# Sheet1.net
KiCad netlist of a schematic drawn in Altium Designer
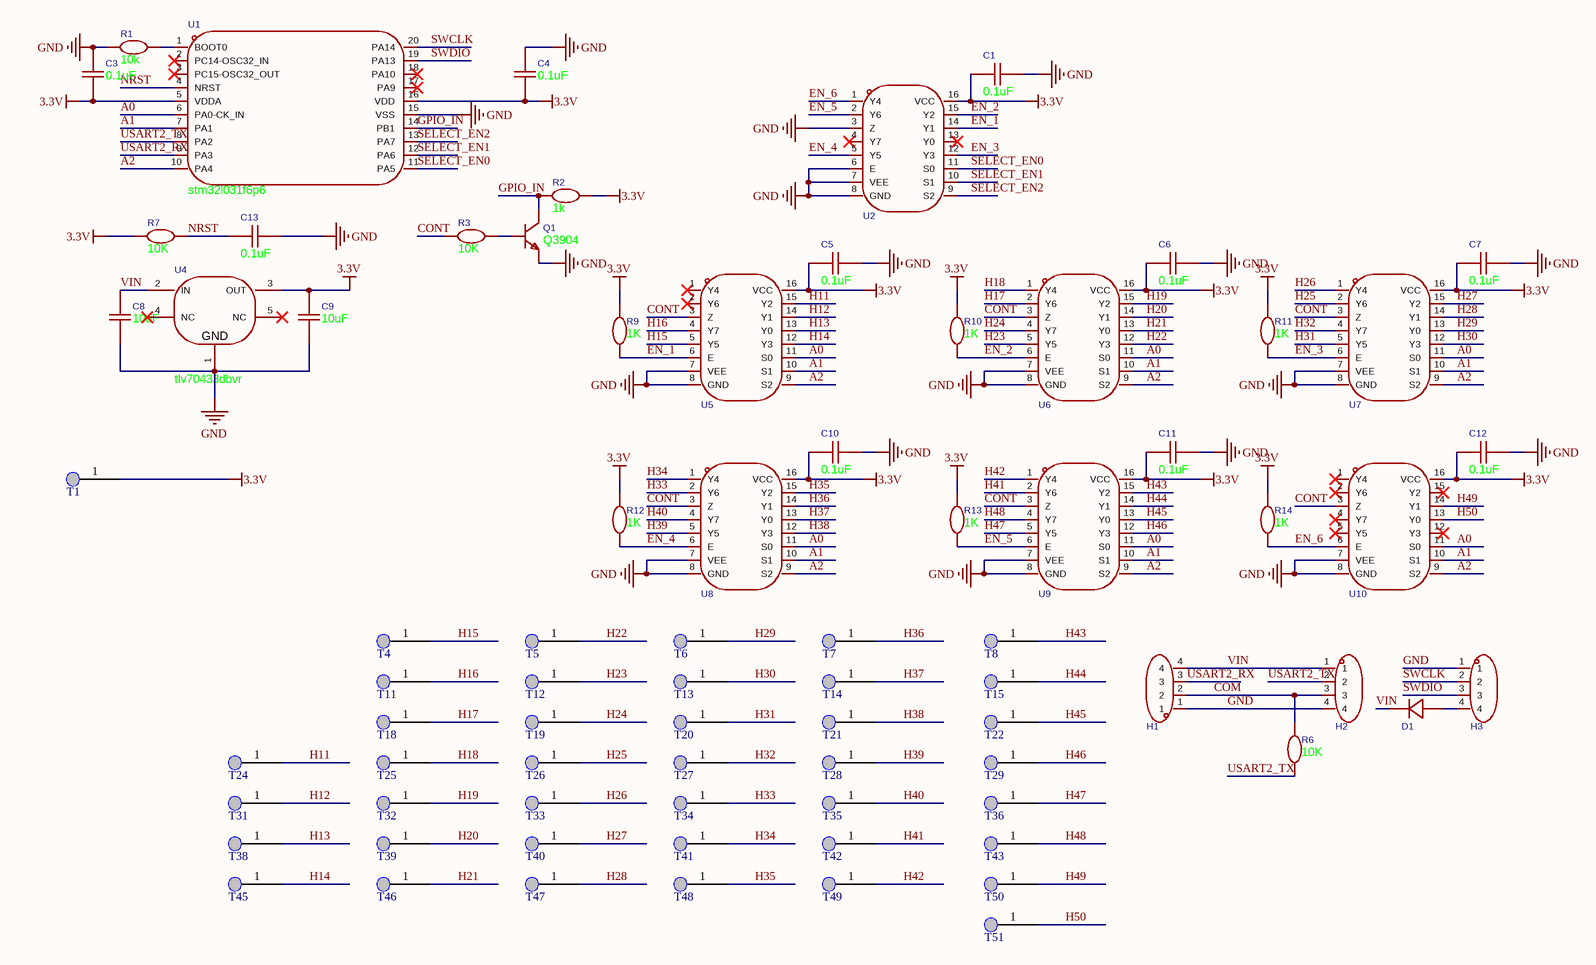
[diagram p0: Sheet1.SchDoc]

(export (version "E")
  (design (tool "Eeschema 10.0.6"))
  (components
    (comp (ref "C1")
      (value "0.1uF")
      (footprint "C0603")
      (description "容值:100nF;精度:±10%;额定电压:50V;温度系数:X7R;")
      (fields (field (name "MANUFACTURER") "SAMSUNG(三星)") (field (name "MANUFACTURERPART") "CL10B104KB8NNNC"))
      (libsource (lib "Schlib1") (part "C"))
    )
    (comp (ref "C3")
      (value "0.1uF")
      (footprint "C0603")
      (description "容值:100nF;精度:±10%;额定电压:50V;温度系数:X7R;")
      (fields (field (name "MANUFACTURER") "SAMSUNG(三星)") (field (name "MANUFACTURERPART") "CL10B104KB8NNNC"))
      (libsource (lib "Schlib1") (part "C"))
    )
    (comp (ref "C4")
      (value "0.1uF")
      (footprint "C0603")
      (description "容值:100nF;精度:±10%;额定电压:50V;温度系数:X7R;")
      (fields (field (name "MANUFACTURER") "SAMSUNG(三星)") (field (name "MANUFACTURERPART") "CL10B104KB8NNNC"))
      (libsource (lib "Schlib1") (part "C"))
    )
    (comp (ref "C5")
      (value "0.1uF")
      (footprint "C0603")
      (description "容值:100nF;精度:±10%;额定电压:50V;温度系数:X7R;")
      (fields (field (name "MANUFACTURER") "SAMSUNG(三星)") (field (name "MANUFACTURERPART") "CL10B104KB8NNNC"))
      (libsource (lib "Schlib1") (part "C"))
    )
    (comp (ref "C6")
      (value "0.1uF")
      (footprint "C0603")
      (description "容值:100nF;精度:±10%;额定电压:50V;温度系数:X7R;")
      (fields (field (name "MANUFACTURER") "SAMSUNG(三星)") (field (name "MANUFACTURERPART") "CL10B104KB8NNNC"))
      (libsource (lib "Schlib1") (part "C"))
    )
    (comp (ref "C7")
      (value "0.1uF")
      (footprint "C0603")
      (description "容值:100nF;精度:±10%;额定电压:50V;温度系数:X7R;")
      (fields (field (name "MANUFACTURER") "SAMSUNG(三星)") (field (name "MANUFACTURERPART") "CL10B104KB8NNNC"))
      (libsource (lib "Schlib1") (part "C"))
    )
    (comp (ref "C8")
      (value "10uF")
      (footprint "C0603")
      (description "容值:100nF;精度:±10%;额定电压:50V;温度系数:X7R;")
      (fields (field (name "MANUFACTURER") "SAMSUNG(三星)") (field (name "MANUFACTURERPART") "CL10B104KB8NNNC"))
      (libsource (lib "Schlib1") (part "C"))
    )
    (comp (ref "C9")
      (value "10uF")
      (footprint "C0603")
      (description "容值:100nF;精度:±10%;额定电压:50V;温度系数:X7R;")
      (fields (field (name "MANUFACTURER") "SAMSUNG(三星)") (field (name "MANUFACTURERPART") "CL10B104KB8NNNC"))
      (libsource (lib "Schlib1") (part "C"))
    )
    (comp (ref "C10")
      (value "0.1uF")
      (footprint "C0603")
      (description "容值:100nF;精度:±10%;额定电压:50V;温度系数:X7R;")
      (fields (field (name "MANUFACTURER") "SAMSUNG(三星)") (field (name "MANUFACTURERPART") "CL10B104KB8NNNC"))
      (libsource (lib "Schlib1") (part "C"))
    )
    (comp (ref "C11")
      (value "0.1uF")
      (footprint "C0603")
      (description "容值:100nF;精度:±10%;额定电压:50V;温度系数:X7R;")
      (fields (field (name "MANUFACTURER") "SAMSUNG(三星)") (field (name "MANUFACTURERPART") "CL10B104KB8NNNC"))
      (libsource (lib "Schlib1") (part "C"))
    )
    (comp (ref "C12")
      (value "0.1uF")
      (footprint "C0603")
      (description "容值:100nF;精度:±10%;额定电压:50V;温度系数:X7R;")
      (fields (field (name "MANUFACTURER") "SAMSUNG(三星)") (field (name "MANUFACTURERPART") "CL10B104KB8NNNC"))
      (libsource (lib "Schlib1") (part "C"))
    )
    (comp (ref "C13")
      (value "0.1uF")
      (footprint "C0603")
      (description "容值:100nF;精度:±10%;额定电压:50V;温度系数:X7R;")
      (fields (field (name "MANUFACTURER") "SAMSUNG(三星)") (field (name "MANUFACTURERPART") "CL10B104KB8NNNC"))
      (libsource (lib "Schlib1") (part "C"))
    )
    (comp (ref "D1")
      (value "1n4148ws_c7420319")
      (footprint "SOD-323_L1.7-W1.3-LS2.5-FD")
      (description "二极管配置:独立式;整流电流:150mA;直流反向耐压(Vr):100V;正向压降(Vf):1.25V@150mA;反向恢复时间(Trr):4ns;")
      (fields (field (name "MANUFACTURER") "R+O(宏嘉诚)") (field (name "MANUFACTURERPART") "1N4148WS"))
      (libsource (lib "Schlib1") (part "1n4148ws_c7420319"))
    )
    (comp (ref "H1")
      (value "pz254v-11-04p")
      (footprint "HDR-TH_4P-P2.54-V-M")
      (fields (field (name "MANUFACTURER") "XFCN(兴飞)") (field (name "MANUFACTURERPART") "PZ254V-11-04P"))
      (libsource (lib "Schlib1") (part "pz254v-11-04p"))
    )
    (comp (ref "H2")
      (value "pz254v-11-04p")
      (footprint "HDR-TH_4P-P2.54-V-M")
      (fields (field (name "MANUFACTURER") "XFCN(兴飞)") (field (name "MANUFACTURERPART") "PZ254V-11-04P"))
      (libsource (lib "Schlib1") (part "pz254v-11-04p"))
    )
    (comp (ref "H3")
      (value "pz254v-11-04p")
      (footprint "HDR-TH_4P-P2.54-V-M")
      (fields (field (name "MANUFACTURER") "XFCN(兴飞)") (field (name "MANUFACTURERPART") "PZ254V-11-04P"))
      (libsource (lib "Schlib1") (part "pz254v-11-04p"))
    )
    (comp (ref "Q1")
      (value "Q3904")
      (footprint "SOT-23-3_L2.9-W1.6-P1.90-LS2.8-BR")
      (description "晶体管类型:NPN;集电极电流(Ic):200mA;集射极击穿电压(Vceo):40V;耗散功率(Pd):225mW;直流电流增益(hFE):40@0.1mA,1.0V;")
      (fields (field (name "MANUFACTURER") "onsemi(安森美)") (field (name "MANUFACTURERPART") "MMBT3904LT1G"))
      (libsource (lib "Schlib1") (part "Q3904"))
    )
    (comp (ref "R1")
      (value "10k")
      (footprint "R0603")
      (description "电阻类型:厚膜电阻;阻值:1kΩ;精度:±1%;功率:100mW;工作电压:75V;温度系数:±100ppm/℃;")
      (fields (field (name "MANUFACTURER") "FOJAN(富捷)") (field (name "MANUFACTURERPART") "FRC0603F1001TS"))
      (libsource (lib "Schlib1") (part "R"))
    )
    (comp (ref "R2")
      (value "1k")
      (footprint "R0603")
      (description "电阻类型:厚膜电阻;阻值:1kΩ;精度:±1%;功率:100mW;工作电压:75V;温度系数:±100ppm/℃;")
      (fields (field (name "MANUFACTURER") "FOJAN(富捷)") (field (name "MANUFACTURERPART") "FRC0603F1001TS"))
      (libsource (lib "Schlib1") (part "R"))
    )
    (comp (ref "R3")
      (value "10K")
      (footprint "R0603")
      (description "电阻类型:厚膜电阻;阻值:1kΩ;精度:±1%;功率:100mW;工作电压:75V;温度系数:±100ppm/℃;")
      (fields (field (name "MANUFACTURER") "FOJAN(富捷)") (field (name "MANUFACTURERPART") "FRC0603F1001TS"))
      (libsource (lib "Schlib1") (part "R"))
    )
    (comp (ref "R6")
      (value "10K")
      (footprint "R0805")
      (description "电阻类型:厚膜电阻;阻值:1kΩ;精度:±1%;功率:100mW;工作电压:75V;温度系数:±100ppm/℃;")
      (fields (field (name "MANUFACTURER") "FOJAN(富捷)") (field (name "MANUFACTURERPART") "FRC0603F1001TS"))
      (libsource (lib "Schlib1") (part "R"))
    )
    (comp (ref "R7")
      (value "10K")
      (footprint "R0603")
      (description "电阻类型:厚膜电阻;阻值:1kΩ;精度:±1%;功率:100mW;工作电压:75V;温度系数:±100ppm/℃;")
      (fields (field (name "MANUFACTURER") "FOJAN(富捷)") (field (name "MANUFACTURERPART") "FRC0603F1001TS"))
      (libsource (lib "Schlib1") (part "R"))
    )
    (comp (ref "R9")
      (value "1K")
      (footprint "R0603")
      (description "电阻类型:厚膜电阻;阻值:1kΩ;精度:±1%;功率:100mW;工作电压:75V;温度系数:±100ppm/℃;")
      (fields (field (name "MANUFACTURER") "FOJAN(富捷)") (field (name "MANUFACTURERPART") "FRC0603F1001TS"))
      (libsource (lib "Schlib1") (part "R"))
    )
    (comp (ref "R10")
      (value "1K")
      (footprint "R0603")
      (description "电阻类型:厚膜电阻;阻值:1kΩ;精度:±1%;功率:100mW;工作电压:75V;温度系数:±100ppm/℃;")
      (fields (field (name "MANUFACTURER") "FOJAN(富捷)") (field (name "MANUFACTURERPART") "FRC0603F1001TS"))
      (libsource (lib "Schlib1") (part "R"))
    )
    (comp (ref "R11")
      (value "1K")
      (footprint "R0603")
      (description "电阻类型:厚膜电阻;阻值:1kΩ;精度:±1%;功率:100mW;工作电压:75V;温度系数:±100ppm/℃;")
      (fields (field (name "MANUFACTURER") "FOJAN(富捷)") (field (name "MANUFACTURERPART") "FRC0603F1001TS"))
      (libsource (lib "Schlib1") (part "R"))
    )
    (comp (ref "R12")
      (value "1K")
      (footprint "R0603")
      (description "电阻类型:厚膜电阻;阻值:1kΩ;精度:±1%;功率:100mW;工作电压:75V;温度系数:±100ppm/℃;")
      (fields (field (name "MANUFACTURER") "FOJAN(富捷)") (field (name "MANUFACTURERPART") "FRC0603F1001TS"))
      (libsource (lib "Schlib1") (part "R"))
    )
    (comp (ref "R13")
      (value "1K")
      (footprint "R0603")
      (description "电阻类型:厚膜电阻;阻值:1kΩ;精度:±1%;功率:100mW;工作电压:75V;温度系数:±100ppm/℃;")
      (fields (field (name "MANUFACTURER") "FOJAN(富捷)") (field (name "MANUFACTURERPART") "FRC0603F1001TS"))
      (libsource (lib "Schlib1") (part "R"))
    )
    (comp (ref "R14")
      (value "1K")
      (footprint "R0603")
      (description "电阻类型:厚膜电阻;阻值:1kΩ;精度:±1%;功率:100mW;工作电压:75V;温度系数:±100ppm/℃;")
      (fields (field (name "MANUFACTURER") "FOJAN(富捷)") (field (name "MANUFACTURERPART") "FRC0603F1001TS"))
      (libsource (lib "Schlib1") (part "R"))
    )
    (comp (ref "T1") (value "焊盘") (footprint "Contact") (libsource (lib "Schlib1") (part "PAD")))
    (comp (ref "T4") (value "焊盘") (footprint "Contact") (libsource (lib "Schlib1") (part "PAD")))
    (comp (ref "T5") (value "焊盘") (footprint "Contact") (libsource (lib "Schlib1") (part "PAD")))
    (comp (ref "T6") (value "焊盘") (footprint "Contact") (libsource (lib "Schlib1") (part "PAD")))
    (comp (ref "T7") (value "焊盘") (footprint "Contact") (libsource (lib "Schlib1") (part "PAD")))
    (comp (ref "T8") (value "焊盘") (footprint "Contact") (libsource (lib "Schlib1") (part "PAD")))
    (comp (ref "T11") (value "焊盘") (footprint "Contact") (libsource (lib "Schlib1") (part "PAD")))
    (comp (ref "T12") (value "焊盘") (footprint "Contact") (libsource (lib "Schlib1") (part "PAD")))
    (comp (ref "T13") (value "焊盘") (footprint "Contact") (libsource (lib "Schlib1") (part "PAD")))
    (comp (ref "T14") (value "焊盘") (footprint "Contact") (libsource (lib "Schlib1") (part "PAD")))
    (comp (ref "T15") (value "焊盘") (footprint "Contact") (libsource (lib "Schlib1") (part "PAD")))
    (comp (ref "T18") (value "焊盘") (footprint "Contact") (libsource (lib "Schlib1") (part "PAD")))
    (comp (ref "T19") (value "焊盘") (footprint "Contact") (libsource (lib "Schlib1") (part "PAD")))
    (comp (ref "T20") (value "焊盘") (footprint "Contact") (libsource (lib "Schlib1") (part "PAD")))
    (comp (ref "T21") (value "焊盘") (footprint "Contact") (libsource (lib "Schlib1") (part "PAD")))
    (comp (ref "T22") (value "焊盘") (footprint "Contact") (libsource (lib "Schlib1") (part "PAD")))
    (comp (ref "T24") (value "焊盘") (footprint "Contact") (libsource (lib "Schlib1") (part "PAD")))
    (comp (ref "T25") (value "焊盘") (footprint "Contact") (libsource (lib "Schlib1") (part "PAD")))
    (comp (ref "T26") (value "焊盘") (footprint "Contact") (libsource (lib "Schlib1") (part "PAD")))
    (comp (ref "T27") (value "焊盘") (footprint "Contact") (libsource (lib "Schlib1") (part "PAD")))
    (comp (ref "T28") (value "焊盘") (footprint "Contact") (libsource (lib "Schlib1") (part "PAD")))
    (comp (ref "T29") (value "焊盘") (footprint "Contact") (libsource (lib "Schlib1") (part "PAD")))
    (comp (ref "T31") (value "焊盘") (footprint "Contact") (libsource (lib "Schlib1") (part "PAD")))
    (comp (ref "T32") (value "焊盘") (footprint "Contact") (libsource (lib "Schlib1") (part "PAD")))
    (comp (ref "T33") (value "焊盘") (footprint "Contact") (libsource (lib "Schlib1") (part "PAD")))
    (comp (ref "T34") (value "焊盘") (footprint "Contact") (libsource (lib "Schlib1") (part "PAD")))
    (comp (ref "T35") (value "焊盘") (footprint "Contact") (libsource (lib "Schlib1") (part "PAD")))
    (comp (ref "T36") (value "焊盘") (footprint "Contact") (libsource (lib "Schlib1") (part "PAD")))
    (comp (ref "T38") (value "焊盘") (footprint "Contact") (libsource (lib "Schlib1") (part "PAD")))
    (comp (ref "T39") (value "焊盘") (footprint "Contact") (libsource (lib "Schlib1") (part "PAD")))
    (comp (ref "T40") (value "焊盘") (footprint "Contact") (libsource (lib "Schlib1") (part "PAD")))
    (comp (ref "T41") (value "焊盘") (footprint "Contact") (libsource (lib "Schlib1") (part "PAD")))
    (comp (ref "T42") (value "焊盘") (footprint "Contact") (libsource (lib "Schlib1") (part "PAD")))
    (comp (ref "T43") (value "焊盘") (footprint "Contact") (libsource (lib "Schlib1") (part "PAD")))
    (comp (ref "T45") (value "焊盘") (footprint "Contact") (libsource (lib "Schlib1") (part "PAD")))
    (comp (ref "T46") (value "焊盘") (footprint "Contact") (libsource (lib "Schlib1") (part "PAD")))
    (comp (ref "T47") (value "焊盘") (footprint "Contact") (libsource (lib "Schlib1") (part "PAD")))
    (comp (ref "T48") (value "焊盘") (footprint "Contact") (libsource (lib "Schlib1") (part "PAD")))
    (comp (ref "T49") (value "焊盘") (footprint "Contact") (libsource (lib "Schlib1") (part "PAD")))
    (comp (ref "T50") (value "焊盘") (footprint "Contact") (libsource (lib "Schlib1") (part "PAD")))
    (comp (ref "T51") (value "焊盘") (footprint "Contact") (libsource (lib "Schlib1") (part "PAD")))
    (comp (ref "U1")
      (value "stm32l031f6p6")
      (footprint "TSSOP-20_L6.5-W4.4-P0.65-LS6.4-BL")
      (description "CPU内核:-;CPU最大主频:32MHz;")
      (fields (field (name "MANUFACTURER") "ST(意法半导体)") (field (name "MANUFACTURERPART") "STM32L031F6P6"))
      (libsource (lib "Schlib1") (part "stm32l031f6p6"))
    )
    (comp (ref "U2")
      (value "74hc4051d,653")
      (footprint "SOIC-16_L9.9-W3.9-P1.27-LS6.0-BL")
      (description "开关电路:8:1;通道数:1;导通电阻(Ron):80Ω;")
      (fields (field (name "MANUFACTURER") "Nexperia(安世)") (field (name "MANUFACTURERPART") "74HC4051D,653"))
      (libsource (lib "Schlib1") (part "74hc4051d,653"))
    )
    (comp (ref "U4")
      (value "tlv70433dbvr")
      (footprint "SOT-23-5_L3.0-W1.7-P0.95-LS2.8-BR")
      (description "输出极性:正极;工作电压:24V;输出电压:3.3V;输出电流:150mA;电源纹波抑制比(PSRR):60dB@(100kHz);输出类型:固定;")
      (fields (field (name "MANUFACTURER") "TI(德州仪器)") (field (name "MANUFACTURERPART") "TLV70433DBVR"))
      (libsource (lib "Schlib1") (part "tlv70433dbvr"))
    )
    (comp (ref "U5")
      (value "74hc4051d,653")
      (footprint "SOIC-16_L9.9-W3.9-P1.27-LS6.0-BL")
      (description "开关电路:8:1;通道数:1;导通电阻(Ron):80Ω;")
      (fields (field (name "MANUFACTURER") "Nexperia(安世)") (field (name "MANUFACTURERPART") "74HC4051D,653"))
      (libsource (lib "Schlib1") (part "74hc4051d,653"))
    )
    (comp (ref "U6")
      (value "74hc4051d,653")
      (footprint "SOIC-16_L9.9-W3.9-P1.27-LS6.0-BL")
      (description "开关电路:8:1;通道数:1;导通电阻(Ron):80Ω;")
      (fields (field (name "MANUFACTURER") "Nexperia(安世)") (field (name "MANUFACTURERPART") "74HC4051D,653"))
      (libsource (lib "Schlib1") (part "74hc4051d,653"))
    )
    (comp (ref "U7")
      (value "74hc4051d,653")
      (footprint "SOIC-16_L9.9-W3.9-P1.27-LS6.0-BL")
      (description "开关电路:8:1;通道数:1;导通电阻(Ron):80Ω;")
      (fields (field (name "MANUFACTURER") "Nexperia(安世)") (field (name "MANUFACTURERPART") "74HC4051D,653"))
      (libsource (lib "Schlib1") (part "74hc4051d,653"))
    )
    (comp (ref "U8")
      (value "74hc4051d,653")
      (footprint "SOIC-16_L9.9-W3.9-P1.27-LS6.0-BL")
      (description "开关电路:8:1;通道数:1;导通电阻(Ron):80Ω;")
      (fields (field (name "MANUFACTURER") "Nexperia(安世)") (field (name "MANUFACTURERPART") "74HC4051D,653"))
      (libsource (lib "Schlib1") (part "74hc4051d,653"))
    )
    (comp (ref "U9")
      (value "74hc4051d,653")
      (footprint "SOIC-16_L9.9-W3.9-P1.27-LS6.0-BL")
      (description "开关电路:8:1;通道数:1;导通电阻(Ron):80Ω;")
      (fields (field (name "MANUFACTURER") "Nexperia(安世)") (field (name "MANUFACTURERPART") "74HC4051D,653"))
      (libsource (lib "Schlib1") (part "74hc4051d,653"))
    )
    (comp (ref "U10")
      (value "74hc4051d,653")
      (footprint "SOIC-16_L9.9-W3.9-P1.27-LS6.0-BL")
      (description "开关电路:8:1;通道数:1;导通电阻(Ron):80Ω;")
      (fields (field (name "MANUFACTURER") "Nexperia(安世)") (field (name "MANUFACTURERPART") "74HC4051D,653"))
      (libsource (lib "Schlib1") (part "74hc4051d,653"))
    )
  )
  (nets
    (net (code "1") (name "/A0") (class "Default")
      (node (ref "U1") (pin "6") (pinfunction "PA0-CK_IN_6") (pintype "passive"))
      (node (ref "U10") (pin "11") (pinfunction "S0_11") (pintype "passive"))
      (node (ref "U5") (pin "11") (pinfunction "S0_11") (pintype "passive"))
      (node (ref "U6") (pin "11") (pinfunction "S0_11") (pintype "passive"))
      (node (ref "U7") (pin "11") (pinfunction "S0_11") (pintype "passive"))
      (node (ref "U8") (pin "11") (pinfunction "S0_11") (pintype "passive"))
      (node (ref "U9") (pin "11") (pinfunction "S0_11") (pintype "passive"))
    )
    (net (code "2") (name "/A1") (class "Default")
      (node (ref "U1") (pin "7") (pinfunction "PA1_7") (pintype "passive"))
      (node (ref "U10") (pin "10") (pinfunction "S1_10") (pintype "passive"))
      (node (ref "U5") (pin "10") (pinfunction "S1_10") (pintype "passive"))
      (node (ref "U6") (pin "10") (pinfunction "S1_10") (pintype "passive"))
      (node (ref "U7") (pin "10") (pinfunction "S1_10") (pintype "passive"))
      (node (ref "U8") (pin "10") (pinfunction "S1_10") (pintype "passive"))
      (node (ref "U9") (pin "10") (pinfunction "S1_10") (pintype "passive"))
    )
    (net (code "3") (name "/A2") (class "Default")
      (node (ref "U1") (pin "10") (pinfunction "PA4_10") (pintype "passive"))
      (node (ref "U10") (pin "9") (pinfunction "S2_9") (pintype "passive"))
      (node (ref "U5") (pin "9") (pinfunction "S2_9") (pintype "passive"))
      (node (ref "U6") (pin "9") (pinfunction "S2_9") (pintype "passive"))
      (node (ref "U7") (pin "9") (pinfunction "S2_9") (pintype "passive"))
      (node (ref "U8") (pin "9") (pinfunction "S2_9") (pintype "passive"))
      (node (ref "U9") (pin "9") (pinfunction "S2_9") (pintype "passive"))
    )
    (net (code "4") (name "/COM") (class "Default")
      (node (ref "H1") (pin "2") (pinfunction "2_2") (pintype "passive"))
      (node (ref "H2") (pin "3") (pinfunction "3_3") (pintype "passive"))
      (node (ref "R6") (pin "2") (pinfunction "2_2") (pintype "passive"))
    )
    (net (code "5") (name "/CONT") (class "Default")
      (node (ref "R3") (pin "1") (pinfunction "1_1") (pintype "passive"))
      (node (ref "U10") (pin "3") (pinfunction "Z_3") (pintype "passive"))
      (node (ref "U5") (pin "3") (pinfunction "Z_3") (pintype "passive"))
      (node (ref "U6") (pin "3") (pinfunction "Z_3") (pintype "passive"))
      (node (ref "U7") (pin "3") (pinfunction "Z_3") (pintype "passive"))
      (node (ref "U8") (pin "3") (pinfunction "Z_3") (pintype "passive"))
      (node (ref "U9") (pin "3") (pinfunction "Z_3") (pintype "passive"))
    )
    (net (code "6") (name "/EN_1") (class "Default")
      (node (ref "R9") (pin "1") (pinfunction "1_1") (pintype "passive"))
      (node (ref "U2") (pin "14") (pinfunction "Y1_14") (pintype "passive"))
      (node (ref "U5") (pin "6") (pinfunction "E_6") (pintype "passive"))
    )
    (net (code "7") (name "/EN_2") (class "Default")
      (node (ref "R10") (pin "1") (pinfunction "1_1") (pintype "passive"))
      (node (ref "U2") (pin "15") (pinfunction "Y2_15") (pintype "passive"))
      (node (ref "U6") (pin "6") (pinfunction "E_6") (pintype "passive"))
    )
    (net (code "8") (name "/EN_3") (class "Default")
      (node (ref "R11") (pin "1") (pinfunction "1_1") (pintype "passive"))
      (node (ref "U2") (pin "12") (pinfunction "Y3_12") (pintype "passive"))
      (node (ref "U7") (pin "6") (pinfunction "E_6") (pintype "passive"))
    )
    (net (code "9") (name "/EN_4") (class "Default")
      (node (ref "R12") (pin "1") (pinfunction "1_1") (pintype "passive"))
      (node (ref "U2") (pin "5") (pinfunction "Y5_5") (pintype "passive"))
      (node (ref "U8") (pin "6") (pinfunction "E_6") (pintype "passive"))
    )
    (net (code "10") (name "/EN_5") (class "Default")
      (node (ref "R13") (pin "1") (pinfunction "1_1") (pintype "passive"))
      (node (ref "U2") (pin "2") (pinfunction "Y6_2") (pintype "passive"))
      (node (ref "U9") (pin "6") (pinfunction "E_6") (pintype "passive"))
    )
    (net (code "11") (name "/EN_6") (class "Default")
      (node (ref "R14") (pin "1") (pinfunction "1_1") (pintype "passive"))
      (node (ref "U10") (pin "6") (pinfunction "E_6") (pintype "passive"))
      (node (ref "U2") (pin "1") (pinfunction "Y4_1") (pintype "passive"))
    )
    (net (code "12") (name "/GPIO_IN") (class "Default")
      (node (ref "Q1") (pin "3") (pinfunction "3_3") (pintype "passive"))
      (node (ref "R2") (pin "2") (pinfunction "2_2") (pintype "passive"))
      (node (ref "U1") (pin "14") (pinfunction "PB1_14") (pintype "passive"))
    )
    (net (code "13") (name "/H11") (class "Default")
      (node (ref "T24") (pin "1") (pintype "passive"))
      (node (ref "U5") (pin "15") (pinfunction "Y2_15") (pintype "passive"))
    )
    (net (code "14") (name "/H12") (class "Default")
      (node (ref "T31") (pin "1") (pintype "passive"))
      (node (ref "U5") (pin "14") (pinfunction "Y1_14") (pintype "passive"))
    )
    (net (code "15") (name "/H13") (class "Default")
      (node (ref "T38") (pin "1") (pintype "passive"))
      (node (ref "U5") (pin "13") (pinfunction "Y0_13") (pintype "passive"))
    )
    (net (code "16") (name "/H14") (class "Default")
      (node (ref "T45") (pin "1") (pintype "passive"))
      (node (ref "U5") (pin "12") (pinfunction "Y3_12") (pintype "passive"))
    )
    (net (code "17") (name "/H15") (class "Default")
      (node (ref "T4") (pin "1") (pintype "passive"))
      (node (ref "U5") (pin "5") (pinfunction "Y5_5") (pintype "passive"))
    )
    (net (code "18") (name "/H16") (class "Default")
      (node (ref "T11") (pin "1") (pintype "passive"))
      (node (ref "U5") (pin "4") (pinfunction "Y7_4") (pintype "passive"))
    )
    (net (code "19") (name "/H17") (class "Default")
      (node (ref "T18") (pin "1") (pintype "passive"))
      (node (ref "U6") (pin "2") (pinfunction "Y6_2") (pintype "passive"))
    )
    (net (code "20") (name "/H18") (class "Default")
      (node (ref "T25") (pin "1") (pintype "passive"))
      (node (ref "U6") (pin "1") (pinfunction "Y4_1") (pintype "passive"))
    )
    (net (code "21") (name "/H19") (class "Default")
      (node (ref "T32") (pin "1") (pintype "passive"))
      (node (ref "U6") (pin "15") (pinfunction "Y2_15") (pintype "passive"))
    )
    (net (code "22") (name "/H20") (class "Default")
      (node (ref "T39") (pin "1") (pintype "passive"))
      (node (ref "U6") (pin "14") (pinfunction "Y1_14") (pintype "passive"))
    )
    (net (code "23") (name "/H21") (class "Default")
      (node (ref "T46") (pin "1") (pintype "passive"))
      (node (ref "U6") (pin "13") (pinfunction "Y0_13") (pintype "passive"))
    )
    (net (code "24") (name "/H22") (class "Default")
      (node (ref "T5") (pin "1") (pintype "passive"))
      (node (ref "U6") (pin "12") (pinfunction "Y3_12") (pintype "passive"))
    )
    (net (code "25") (name "/H23") (class "Default")
      (node (ref "T12") (pin "1") (pintype "passive"))
      (node (ref "U6") (pin "5") (pinfunction "Y5_5") (pintype "passive"))
    )
    (net (code "26") (name "/H24") (class "Default")
      (node (ref "T19") (pin "1") (pintype "passive"))
      (node (ref "U6") (pin "4") (pinfunction "Y7_4") (pintype "passive"))
    )
    (net (code "27") (name "/H25") (class "Default")
      (node (ref "T26") (pin "1") (pintype "passive"))
      (node (ref "U7") (pin "2") (pinfunction "Y6_2") (pintype "passive"))
    )
    (net (code "28") (name "/H26") (class "Default")
      (node (ref "T33") (pin "1") (pintype "passive"))
      (node (ref "U7") (pin "1") (pinfunction "Y4_1") (pintype "passive"))
    )
    (net (code "29") (name "/H27") (class "Default")
      (node (ref "T40") (pin "1") (pintype "passive"))
      (node (ref "U7") (pin "15") (pinfunction "Y2_15") (pintype "passive"))
    )
    (net (code "30") (name "/H28") (class "Default")
      (node (ref "T47") (pin "1") (pintype "passive"))
      (node (ref "U7") (pin "14") (pinfunction "Y1_14") (pintype "passive"))
    )
    (net (code "31") (name "/H29") (class "Default")
      (node (ref "T6") (pin "1") (pintype "passive"))
      (node (ref "U7") (pin "13") (pinfunction "Y0_13") (pintype "passive"))
    )
    (net (code "32") (name "/H30") (class "Default")
      (node (ref "T13") (pin "1") (pintype "passive"))
      (node (ref "U7") (pin "12") (pinfunction "Y3_12") (pintype "passive"))
    )
    (net (code "33") (name "/H31") (class "Default")
      (node (ref "T20") (pin "1") (pintype "passive"))
      (node (ref "U7") (pin "5") (pinfunction "Y5_5") (pintype "passive"))
    )
    (net (code "34") (name "/H32") (class "Default")
      (node (ref "T27") (pin "1") (pintype "passive"))
      (node (ref "U7") (pin "4") (pinfunction "Y7_4") (pintype "passive"))
    )
    (net (code "35") (name "/H33") (class "Default")
      (node (ref "T34") (pin "1") (pintype "passive"))
      (node (ref "U8") (pin "2") (pinfunction "Y6_2") (pintype "passive"))
    )
    (net (code "36") (name "/H34") (class "Default")
      (node (ref "T41") (pin "1") (pintype "passive"))
      (node (ref "U8") (pin "1") (pinfunction "Y4_1") (pintype "passive"))
    )
    (net (code "37") (name "/H35") (class "Default")
      (node (ref "T48") (pin "1") (pintype "passive"))
      (node (ref "U8") (pin "15") (pinfunction "Y2_15") (pintype "passive"))
    )
    (net (code "38") (name "/H36") (class "Default")
      (node (ref "T7") (pin "1") (pintype "passive"))
      (node (ref "U8") (pin "14") (pinfunction "Y1_14") (pintype "passive"))
    )
    (net (code "39") (name "/H37") (class "Default")
      (node (ref "T14") (pin "1") (pintype "passive"))
      (node (ref "U8") (pin "13") (pinfunction "Y0_13") (pintype "passive"))
    )
    (net (code "40") (name "/H38") (class "Default")
      (node (ref "T21") (pin "1") (pintype "passive"))
      (node (ref "U8") (pin "12") (pinfunction "Y3_12") (pintype "passive"))
    )
    (net (code "41") (name "/H39") (class "Default")
      (node (ref "T28") (pin "1") (pintype "passive"))
      (node (ref "U8") (pin "5") (pinfunction "Y5_5") (pintype "passive"))
    )
    (net (code "42") (name "/H40") (class "Default")
      (node (ref "T35") (pin "1") (pintype "passive"))
      (node (ref "U8") (pin "4") (pinfunction "Y7_4") (pintype "passive"))
    )
    (net (code "43") (name "/H41") (class "Default")
      (node (ref "T42") (pin "1") (pintype "passive"))
      (node (ref "U9") (pin "2") (pinfunction "Y6_2") (pintype "passive"))
    )
    (net (code "44") (name "/H42") (class "Default")
      (node (ref "T49") (pin "1") (pintype "passive"))
      (node (ref "U9") (pin "1") (pinfunction "Y4_1") (pintype "passive"))
    )
    (net (code "45") (name "/H43") (class "Default")
      (node (ref "T8") (pin "1") (pintype "passive"))
      (node (ref "U9") (pin "15") (pinfunction "Y2_15") (pintype "passive"))
    )
    (net (code "46") (name "/H44") (class "Default")
      (node (ref "T15") (pin "1") (pintype "passive"))
      (node (ref "U9") (pin "14") (pinfunction "Y1_14") (pintype "passive"))
    )
    (net (code "47") (name "/H45") (class "Default")
      (node (ref "T22") (pin "1") (pintype "passive"))
      (node (ref "U9") (pin "13") (pinfunction "Y0_13") (pintype "passive"))
    )
    (net (code "48") (name "/H46") (class "Default")
      (node (ref "T29") (pin "1") (pintype "passive"))
      (node (ref "U9") (pin "12") (pinfunction "Y3_12") (pintype "passive"))
    )
    (net (code "49") (name "/H47") (class "Default")
      (node (ref "T36") (pin "1") (pintype "passive"))
      (node (ref "U9") (pin "5") (pinfunction "Y5_5") (pintype "passive"))
    )
    (net (code "50") (name "/H48") (class "Default")
      (node (ref "T43") (pin "1") (pintype "passive"))
      (node (ref "U9") (pin "4") (pinfunction "Y7_4") (pintype "passive"))
    )
    (net (code "51") (name "/H49") (class "Default")
      (node (ref "T50") (pin "1") (pintype "passive"))
      (node (ref "U10") (pin "14") (pinfunction "Y1_14") (pintype "passive"))
    )
    (net (code "52") (name "/H50") (class "Default")
      (node (ref "T51") (pin "1") (pintype "passive"))
      (node (ref "U10") (pin "13") (pinfunction "Y0_13") (pintype "passive"))
    )
    (net (code "53") (name "/NRST") (class "Default")
      (node (ref "C13") (pin "1") (pinfunction "1_1") (pintype "passive"))
      (node (ref "R7") (pin "2") (pinfunction "2_2") (pintype "passive"))
      (node (ref "U1") (pin "4") (pinfunction "NRST_4") (pintype "passive"))
    )
    (net (code "54") (name "/SELECT_EN0") (class "Default")
      (node (ref "U1") (pin "11") (pinfunction "PA5_11") (pintype "passive"))
      (node (ref "U2") (pin "11") (pinfunction "S0_11") (pintype "passive"))
    )
    (net (code "55") (name "/SELECT_EN1") (class "Default")
      (node (ref "U1") (pin "12") (pinfunction "PA6_12") (pintype "passive"))
      (node (ref "U2") (pin "10") (pinfunction "S1_10") (pintype "passive"))
    )
    (net (code "56") (name "/SELECT_EN2") (class "Default")
      (node (ref "U1") (pin "13") (pinfunction "PA7_13") (pintype "passive"))
      (node (ref "U2") (pin "9") (pinfunction "S2_9") (pintype "passive"))
    )
    (net (code "57") (name "/SWCLK") (class "Default")
      (node (ref "H3") (pin "2") (pinfunction "2_2") (pintype "passive"))
      (node (ref "U1") (pin "20") (pinfunction "PA14_20") (pintype "passive"))
    )
    (net (code "58") (name "/SWDIO") (class "Default")
      (node (ref "H3") (pin "3") (pinfunction "3_3") (pintype "passive"))
      (node (ref "U1") (pin "19") (pinfunction "PA13_19") (pintype "passive"))
    )
    (net (code "59") (name "/USART2_RX") (class "Default")
      (node (ref "H1") (pin "3") (pinfunction "3_3") (pintype "passive"))
      (node (ref "U1") (pin "9") (pinfunction "PA3_9") (pintype "passive"))
    )
    (net (code "60") (name "/USART2_TX") (class "Default")
      (node (ref "H2") (pin "2") (pinfunction "2_2") (pintype "passive"))
      (node (ref "R6") (pin "1") (pinfunction "1_1") (pintype "passive"))
      (node (ref "U1") (pin "8") (pinfunction "PA2_8") (pintype "passive"))
    )
    (net (code "61") (name "/VIN") (class "Default")
      (node (ref "C8") (pin "2") (pinfunction "2_2") (pintype "passive"))
      (node (ref "D1") (pin "2") (pinfunction "K_2") (pintype "passive"))
      (node (ref "H1") (pin "4") (pinfunction "4_4") (pintype "passive"))
      (node (ref "H2") (pin "1") (pinfunction "1_1") (pintype "passive"))
      (node (ref "U4") (pin "2") (pinfunction "IN_2") (pintype "passive"))
    )
    (net (code "62") (name "3.3V") (class "Default")
      (node (ref "C1") (pin "2") (pinfunction "2_2") (pintype "passive"))
      (node (ref "C10") (pin "2") (pinfunction "2_2") (pintype "passive"))
      (node (ref "C11") (pin "2") (pinfunction "2_2") (pintype "passive"))
      (node (ref "C12") (pin "2") (pinfunction "2_2") (pintype "passive"))
      (node (ref "C3") (pin "1") (pinfunction "1_1") (pintype "passive"))
      (node (ref "C4") (pin "1") (pinfunction "1_1") (pintype "passive"))
      (node (ref "C5") (pin "2") (pinfunction "2_2") (pintype "passive"))
      (node (ref "C6") (pin "2") (pinfunction "2_2") (pintype "passive"))
      (node (ref "C7") (pin "2") (pinfunction "2_2") (pintype "passive"))
      (node (ref "C9") (pin "2") (pinfunction "2_2") (pintype "passive"))
      (node (ref "R10") (pin "2") (pinfunction "2_2") (pintype "passive"))
      (node (ref "R11") (pin "2") (pinfunction "2_2") (pintype "passive"))
      (node (ref "R12") (pin "2") (pinfunction "2_2") (pintype "passive"))
      (node (ref "R13") (pin "2") (pinfunction "2_2") (pintype "passive"))
      (node (ref "R14") (pin "2") (pinfunction "2_2") (pintype "passive"))
      (node (ref "R2") (pin "1") (pinfunction "1_1") (pintype "passive"))
      (node (ref "R7") (pin "1") (pinfunction "1_1") (pintype "passive"))
      (node (ref "R9") (pin "2") (pinfunction "2_2") (pintype "passive"))
      (node (ref "T1") (pin "1") (pintype "passive"))
      (node (ref "U1") (pin "16") (pinfunction "VDD_16") (pintype "passive"))
      (node (ref "U1") (pin "5") (pinfunction "VDDA_5") (pintype "passive"))
      (node (ref "U10") (pin "16") (pinfunction "VCC_16") (pintype "passive"))
      (node (ref "U2") (pin "16") (pinfunction "VCC_16") (pintype "passive"))
      (node (ref "U4") (pin "3") (pinfunction "OUT_3") (pintype "passive"))
      (node (ref "U5") (pin "16") (pinfunction "VCC_16") (pintype "passive"))
      (node (ref "U6") (pin "16") (pinfunction "VCC_16") (pintype "passive"))
      (node (ref "U7") (pin "16") (pinfunction "VCC_16") (pintype "passive"))
      (node (ref "U8") (pin "16") (pinfunction "VCC_16") (pintype "passive"))
      (node (ref "U9") (pin "16") (pinfunction "VCC_16") (pintype "passive"))
    )
    (net (code "63") (name "GND") (class "Default")
      (node (ref "C1") (pin "1") (pinfunction "1_1") (pintype "passive"))
      (node (ref "C10") (pin "1") (pinfunction "1_1") (pintype "passive"))
      (node (ref "C11") (pin "1") (pinfunction "1_1") (pintype "passive"))
      (node (ref "C12") (pin "1") (pinfunction "1_1") (pintype "passive"))
      (node (ref "C13") (pin "2") (pinfunction "2_2") (pintype "passive"))
      (node (ref "C3") (pin "2") (pinfunction "2_2") (pintype "passive"))
      (node (ref "C4") (pin "2") (pinfunction "2_2") (pintype "passive"))
      (node (ref "C5") (pin "1") (pinfunction "1_1") (pintype "passive"))
      (node (ref "C6") (pin "1") (pinfunction "1_1") (pintype "passive"))
      (node (ref "C7") (pin "1") (pinfunction "1_1") (pintype "passive"))
      (node (ref "C8") (pin "1") (pinfunction "1_1") (pintype "passive"))
      (node (ref "C9") (pin "1") (pinfunction "1_1") (pintype "passive"))
      (node (ref "H1") (pin "1") (pinfunction "1_1") (pintype "passive"))
      (node (ref "H2") (pin "4") (pinfunction "4_4") (pintype "passive"))
      (node (ref "H3") (pin "1") (pinfunction "1_1") (pintype "passive"))
      (node (ref "Q1") (pin "2") (pinfunction "2_2") (pintype "passive"))
      (node (ref "R1") (pin "1") (pinfunction "1_1") (pintype "passive"))
      (node (ref "U1") (pin "15") (pinfunction "VSS_15") (pintype "passive"))
      (node (ref "U10") (pin "7") (pinfunction "VEE_7") (pintype "passive"))
      (node (ref "U10") (pin "8") (pinfunction "GND_8") (pintype "passive"))
      (node (ref "U2") (pin "3") (pinfunction "Z_3") (pintype "passive"))
      (node (ref "U2") (pin "6") (pinfunction "E_6") (pintype "passive"))
      (node (ref "U2") (pin "7") (pinfunction "VEE_7") (pintype "passive"))
      (node (ref "U2") (pin "8") (pinfunction "GND_8") (pintype "passive"))
      (node (ref "U4") (pin "1") (pinfunction "GND_1") (pintype "passive"))
      (node (ref "U5") (pin "7") (pinfunction "VEE_7") (pintype "passive"))
      (node (ref "U5") (pin "8") (pinfunction "GND_8") (pintype "passive"))
      (node (ref "U6") (pin "7") (pinfunction "VEE_7") (pintype "passive"))
      (node (ref "U6") (pin "8") (pinfunction "GND_8") (pintype "passive"))
      (node (ref "U7") (pin "7") (pinfunction "VEE_7") (pintype "passive"))
      (node (ref "U7") (pin "8") (pinfunction "GND_8") (pintype "passive"))
      (node (ref "U8") (pin "7") (pinfunction "VEE_7") (pintype "passive"))
      (node (ref "U8") (pin "8") (pinfunction "GND_8") (pintype "passive"))
      (node (ref "U9") (pin "7") (pinfunction "VEE_7") (pintype "passive"))
      (node (ref "U9") (pin "8") (pinfunction "GND_8") (pintype "passive"))
    )
    (net (code "64") (name "Net-(D1-A)") (class "Default")
      (node (ref "D1") (pin "1") (pinfunction "A_1") (pintype "passive"))
      (node (ref "H3") (pin "4") (pinfunction "4_4") (pintype "passive"))
    )
    (net (code "65") (name "Net-(Q1-Pad1)") (class "Default")
      (node (ref "Q1") (pin "1") (pinfunction "1_1") (pintype "passive"))
      (node (ref "R3") (pin "2") (pinfunction "2_2") (pintype "passive"))
    )
    (net (code "66") (name "Net-(U1-BOOT0)") (class "Default")
      (node (ref "R1") (pin "2") (pinfunction "2_2") (pintype "passive"))
      (node (ref "U1") (pin "1") (pinfunction "BOOT0_1") (pintype "passive"))
    )
    (net (code "67") (name "unconnected-(U1-PA9-Pad17)") (class "Default")
      (node (ref "U1") (pin "17") (pinfunction "PA9_17") (pintype "passive+no_connect"))
    )
    (net (code "68") (name "unconnected-(U1-PA10-Pad18)") (class "Default")
      (node (ref "U1") (pin "18") (pinfunction "PA10_18") (pintype "passive+no_connect"))
    )
    (net (code "69") (name "unconnected-(U1-PC14-OSC32_IN-Pad2)") (class "Default")
      (node (ref "U1") (pin "2") (pinfunction "PC14-OSC32_IN_2") (pintype "passive+no_connect"))
    )
    (net (code "70") (name "unconnected-(U1-PC15-OSC32_OUT-Pad3)") (class "Default")
      (node (ref "U1") (pin "3") (pinfunction "PC15-OSC32_OUT_3") (pintype "passive+no_connect"))
    )
    (net (code "71") (name "unconnected-(U2-Y0-Pad13)") (class "Default")
      (node (ref "U2") (pin "13") (pinfunction "Y0_13") (pintype "passive+no_connect"))
    )
    (net (code "72") (name "unconnected-(U2-Y7-Pad4)") (class "Default")
      (node (ref "U2") (pin "4") (pinfunction "Y7_4") (pintype "passive+no_connect"))
    )
    (net (code "73") (name "unconnected-(U4-NC-Pad4)") (class "Default")
      (node (ref "U4") (pin "4") (pinfunction "NC_4") (pintype "passive+no_connect"))
    )
    (net (code "74") (name "unconnected-(U4-NC-Pad5)") (class "Default")
      (node (ref "U4") (pin "5") (pinfunction "NC_5") (pintype "passive+no_connect"))
    )
    (net (code "75") (name "unconnected-(U5-Y4-Pad1)") (class "Default")
      (node (ref "U5") (pin "1") (pinfunction "Y4_1") (pintype "passive+no_connect"))
    )
    (net (code "76") (name "unconnected-(U5-Y6-Pad2)") (class "Default")
      (node (ref "U5") (pin "2") (pinfunction "Y6_2") (pintype "passive+no_connect"))
    )
    (net (code "77") (name "unconnected-(U10-Y2-Pad15)") (class "Default")
      (node (ref "U10") (pin "15") (pinfunction "Y2_15") (pintype "passive+no_connect"))
    )
    (net (code "78") (name "unconnected-(U10-Y3-Pad12)") (class "Default")
      (node (ref "U10") (pin "12") (pinfunction "Y3_12") (pintype "passive+no_connect"))
    )
    (net (code "79") (name "unconnected-(U10-Y4-Pad1)") (class "Default")
      (node (ref "U10") (pin "1") (pinfunction "Y4_1") (pintype "passive+no_connect"))
    )
    (net (code "80") (name "unconnected-(U10-Y5-Pad5)") (class "Default")
      (node (ref "U10") (pin "5") (pinfunction "Y5_5") (pintype "passive+no_connect"))
    )
    (net (code "81") (name "unconnected-(U10-Y6-Pad2)") (class "Default")
      (node (ref "U10") (pin "2") (pinfunction "Y6_2") (pintype "passive+no_connect"))
    )
    (net (code "82") (name "unconnected-(U10-Y7-Pad4)") (class "Default")
      (node (ref "U10") (pin "4") (pinfunction "Y7_4") (pintype "passive+no_connect"))
    )
  )
)
